# HFM_SWD.net
KiCad netlist of a schematic drawn in Altium Designer
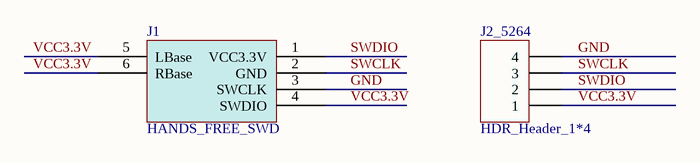
[diagram p0: HFM_SWD.SchDoc]

(export (version "E")
  (design (tool "Eeschema 10.0.6"))
  (components
    (comp (ref "J1")
      (value "HANDS_FREE_SWD")
      (footprint "HDR_Molex_PH_1.25_4P")
      (description "卧贴 molex 1.25间距 4P接口")
      (libsource (lib "Hands_free") (part "HANDS_FREE_SWD"))
    )
    (comp (ref "J2_5264")
      (value "HDR_Header_1*4")
      (footprint "HDR_MOLEX_5264_DH_4P")
      (fields (field (name "PUBLISHER") "Altium Limited"))
      (libsource (lib "Hands_free") (part "HDR_Header_1*4"))
    )
  )
  (nets
    (net (code "1") (name "/GND") (class "Default")
      (node (ref "J1") (pin "3") (pinfunction "SWCLK_3") (pintype "passive"))
      (node (ref "J2_5264") (pin "4") (pinfunction "4_4") (pintype "passive"))
    )
    (net (code "2") (name "/SWCLK") (class "Default")
      (node (ref "J1") (pin "2") (pinfunction "GND_2") (pintype "passive"))
      (node (ref "J2_5264") (pin "3") (pinfunction "3_3") (pintype "passive"))
    )
    (net (code "3") (name "/SWDIO") (class "Default")
      (node (ref "J1") (pin "1") (pinfunction "VCC3.3V_1") (pintype "passive"))
      (node (ref "J2_5264") (pin "2") (pinfunction "2_2") (pintype "passive"))
    )
    (net (code "4") (name "/VCC3.3V") (class "Default")
      (node (ref "J1") (pin "4") (pinfunction "SWDIO_4") (pintype "passive"))
      (node (ref "J1") (pin "5") (pinfunction "LBase_5") (pintype "passive"))
      (node (ref "J1") (pin "6") (pinfunction "RBase_6") (pintype "passive"))
      (node (ref "J2_5264") (pin "1") (pinfunction "1_1") (pintype "passive"))
    )
  )
)
